# espn_board.net
KiCad netlist of a schematic drawn in EAGLE
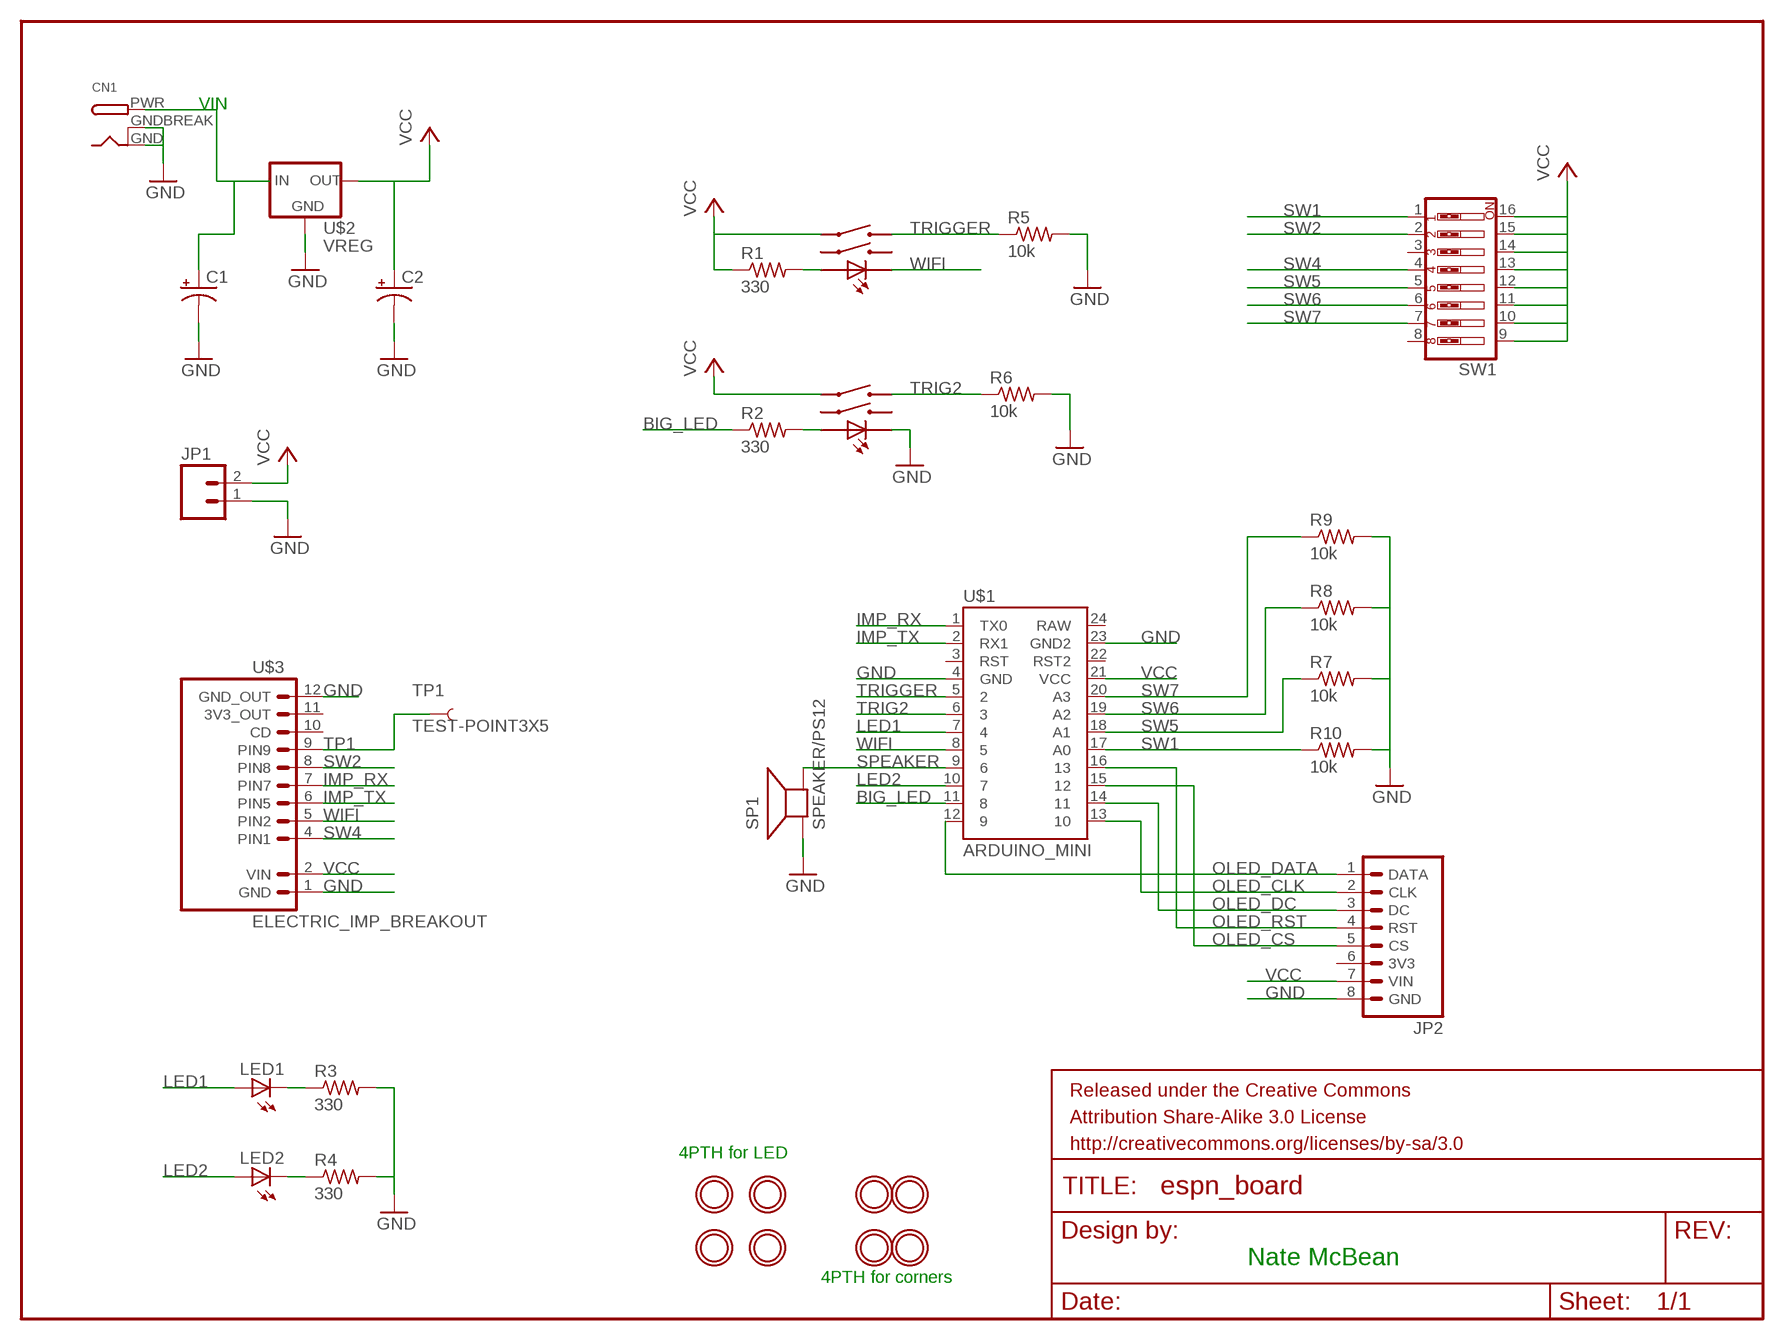
[diagram p0: schematic, sheet 1]

(export (version "E")
  (design (tool "Eeschema 10.0.6"))
  (components
    (comp (ref "ACK")
      (value "LED_TACTILE_BUTTON")
      (footprint "eagle-import:LED_TACTILE_BUTTON")
      (libsource (lib "eagle-import") (part "LED_TACTILE_BUTTON"))
    )
    (comp (ref "C1")
      (value "CAP_POLPTH2")
      (footprint "eagle-import:CPOL-RADIAL-10UF-25V")
      (libsource (lib "eagle-import") (part "CAP_POLPTH2"))
    )
    (comp (ref "C2")
      (value "CAP_POLPTH2")
      (footprint "eagle-import:CPOL-RADIAL-10UF-25V")
      (libsource (lib "eagle-import") (part "CAP_POLPTH2"))
    )
    (comp (ref "CN1")
      (value "DCBARRELPTH")
      (footprint "eagle-import:DCJACK_2MM_PTH")
      (libsource (lib "eagle-import") (part "DCBARRELPTH"))
    )
    (comp (ref "FRAME1")
      (value "FRAME-LETTER")
      (footprint "eagle-import:CREATIVE_COMMONS")
      (libsource (lib "eagle-import") (part "FRAME-LETTER"))
    )
    (comp (ref "JP1")
      (value "M02PTH")
      (footprint "eagle-import:1X02")
      (libsource (lib "eagle-import") (part "M02PTH"))
    )
    (comp (ref "JP2")
      (value "OLED128X641X08")
      (footprint "eagle-import:OLED_128X64")
      (libsource (lib "eagle-import") (part "OLED128X641X08"))
    )
    (comp (ref "LED1")
      (value "LED5MM")
      (footprint "eagle-import:LED5MM")
      (libsource (lib "eagle-import") (part "LED5MM"))
    )
    (comp (ref "LED2")
      (value "LED5MM")
      (footprint "eagle-import:LED5MM")
      (libsource (lib "eagle-import") (part "LED5MM"))
    )
    (comp (ref "R1")
      (value "330")
      (footprint "eagle-import:R0805")
      (libsource (lib "eagle-import") (part "R-US_R0805"))
    )
    (comp (ref "R2")
      (value "330")
      (footprint "eagle-import:R0805")
      (libsource (lib "eagle-import") (part "R-US_R0805"))
    )
    (comp (ref "R3")
      (value "330")
      (footprint "eagle-import:R0805")
      (libsource (lib "eagle-import") (part "R-US_R0805"))
    )
    (comp (ref "R4")
      (value "330")
      (footprint "eagle-import:R0805")
      (libsource (lib "eagle-import") (part "R-US_R0805"))
    )
    (comp (ref "R5")
      (value "10k")
      (footprint "eagle-import:R0805")
      (libsource (lib "eagle-import") (part "R-US_R0805"))
    )
    (comp (ref "R6")
      (value "10k")
      (footprint "eagle-import:R0805")
      (libsource (lib "eagle-import") (part "R-US_R0805"))
    )
    (comp (ref "R7")
      (value "10k")
      (footprint "eagle-import:R0805")
      (libsource (lib "eagle-import") (part "R-US_R0805"))
    )
    (comp (ref "R8")
      (value "10k")
      (footprint "eagle-import:R0805")
      (libsource (lib "eagle-import") (part "R-US_R0805"))
    )
    (comp (ref "R9")
      (value "10k")
      (footprint "eagle-import:R0805")
      (libsource (lib "eagle-import") (part "R-US_R0805"))
    )
    (comp (ref "R10")
      (value "10k")
      (footprint "eagle-import:R0805")
      (libsource (lib "eagle-import") (part "R-US_R0805"))
    )
    (comp (ref "SEND")
      (value "LED_TACTILE_BUTTON")
      (footprint "eagle-import:LED_TACTILE_BUTTON")
      (libsource (lib "eagle-import") (part "LED_TACTILE_BUTTON"))
    )
    (comp (ref "SP1")
      (value "SPEAKER/PS12")
      (footprint "eagle-import:PS12")
      (libsource (lib "eagle-import") (part "SPEAKER/PS12"))
    )
    (comp (ref "SW1")
      (value "SW_DIP-8")
      (footprint "eagle-import:DIPSWITCH-08")
      (libsource (lib "eagle-import") (part "SW_DIP-8"))
    )
    (comp (ref "TP1")
      (value "TEST-POINT3X5")
      (footprint "eagle-import:PAD.03X.05")
      (libsource (lib "eagle-import") (part "TEST-POINT3X5"))
    )
    (comp (ref "U$1")
      (value "ARDUINO_MINI")
      (footprint "eagle-import:ARDUINO_MINI")
      (libsource (lib "eagle-import") (part "ARDUINO_MINI"))
    )
    (comp (ref "U$2")
      (value "VREG")
      (footprint "eagle-import:78XXL")
      (libsource (lib "eagle-import") (part "V_REG_LD1117VXX"))
    )
    (comp (ref "U$3")
      (value "ELECTRIC_IMP_BREAKOUT")
      (footprint "eagle-import:ELECTRIC_IMP_BREAKOUT")
      (libsource (lib "eagle-import") (part "ELECTRIC_IMP_BREAKOUT"))
    )
    (comp (ref "U$5")
      (value "MOUNTINGHOLE2.5")
      (footprint "eagle-import:MOUNTINGHOLE_2.5_PLATED")
      (libsource (lib "eagle-import") (part "MOUNTINGHOLE2.5"))
    )
    (comp (ref "U$6")
      (value "MOUNTINGHOLE2.5")
      (footprint "eagle-import:MOUNTINGHOLE_2.5_PLATED")
      (libsource (lib "eagle-import") (part "MOUNTINGHOLE2.5"))
    )
    (comp (ref "U$7")
      (value "MOUNTINGHOLE2.5")
      (footprint "eagle-import:MOUNTINGHOLE_2.5_PLATED")
      (libsource (lib "eagle-import") (part "MOUNTINGHOLE2.5"))
    )
    (comp (ref "U$8")
      (value "MOUNTINGHOLE2.5")
      (footprint "eagle-import:MOUNTINGHOLE_2.5_PLATED")
      (libsource (lib "eagle-import") (part "MOUNTINGHOLE2.5"))
    )
    (comp (ref "U$9")
      (value "MOUNTINGHOLE2.5")
      (footprint "eagle-import:MOUNTINGHOLE_2.5_PLATED")
      (libsource (lib "eagle-import") (part "MOUNTINGHOLE2.5"))
    )
    (comp (ref "U$10")
      (value "MOUNTINGHOLE2.5")
      (footprint "eagle-import:MOUNTINGHOLE_2.5_PLATED")
      (libsource (lib "eagle-import") (part "MOUNTINGHOLE2.5"))
    )
    (comp (ref "U$11")
      (value "MOUNTINGHOLE2.5")
      (footprint "eagle-import:MOUNTINGHOLE_2.5_PLATED")
      (libsource (lib "eagle-import") (part "MOUNTINGHOLE2.5"))
    )
    (comp (ref "U$12")
      (value "MOUNTINGHOLE2.5")
      (footprint "eagle-import:MOUNTINGHOLE_2.5_PLATED")
      (libsource (lib "eagle-import") (part "MOUNTINGHOLE2.5"))
    )
  )
  (nets
    (net (code "1") (name "/BIG_LED") (class "Default")
      (node (ref "R2") (pin "1") (pinfunction "1_1") (pintype "passive"))
      (node (ref "U$1") (pin "11") (pinfunction "8_11") (pintype "bidirectional"))
    )
    (net (code "2") (name "/IMP_RX") (class "Default")
      (node (ref "U$1") (pin "1") (pinfunction "TX0_1") (pintype "bidirectional"))
      (node (ref "U$3") (pin "7") (pinfunction "PIN7_7") (pintype "passive"))
    )
    (net (code "3") (name "/IMP_TX") (class "Default")
      (node (ref "U$1") (pin "2") (pinfunction "RX1_2") (pintype "bidirectional"))
      (node (ref "U$3") (pin "6") (pinfunction "PIN5_6") (pintype "passive"))
    )
    (net (code "4") (name "/LED1") (class "Default")
      (node (ref "LED1") (pin "A") (pinfunction "A_A") (pintype "passive"))
      (node (ref "U$1") (pin "7") (pinfunction "4_7") (pintype "bidirectional"))
    )
    (net (code "5") (name "/LED2") (class "Default")
      (node (ref "LED2") (pin "A") (pinfunction "A_A") (pintype "passive"))
      (node (ref "U$1") (pin "10") (pinfunction "7_10") (pintype "bidirectional"))
    )
    (net (code "6") (name "/OLED_CLK") (class "Default")
      (node (ref "JP2") (pin "2") (pinfunction "CLK_2") (pintype "passive"))
      (node (ref "U$1") (pin "13") (pinfunction "10_13") (pintype "bidirectional"))
    )
    (net (code "7") (name "/OLED_CS") (class "Default")
      (node (ref "JP2") (pin "5") (pinfunction "CS_5") (pintype "passive"))
      (node (ref "U$1") (pin "15") (pinfunction "12_15") (pintype "bidirectional"))
    )
    (net (code "8") (name "/OLED_DATA") (class "Default")
      (node (ref "JP2") (pin "1") (pinfunction "DATA_1") (pintype "passive"))
      (node (ref "U$1") (pin "12") (pinfunction "9_12") (pintype "bidirectional"))
    )
    (net (code "9") (name "/OLED_DC") (class "Default")
      (node (ref "JP2") (pin "3") (pinfunction "DC_3") (pintype "passive"))
      (node (ref "U$1") (pin "14") (pinfunction "11_14") (pintype "bidirectional"))
    )
    (net (code "10") (name "/OLED_RST") (class "Default")
      (node (ref "JP2") (pin "4") (pinfunction "RST_4") (pintype "passive"))
      (node (ref "U$1") (pin "16") (pinfunction "13_16") (pintype "bidirectional"))
    )
    (net (code "11") (name "/SPEAKER") (class "Default")
      (node (ref "SP1") (pin "P$2") (pinfunction "-_P$2") (pintype "passive"))
      (node (ref "U$1") (pin "9") (pinfunction "6_9") (pintype "bidirectional"))
    )
    (net (code "12") (name "/SW1") (class "Default")
      (node (ref "R10") (pin "1") (pinfunction "1_1") (pintype "passive"))
      (node (ref "SW1") (pin "1") (pinfunction "1_1") (pintype "passive"))
      (node (ref "U$1") (pin "17") (pinfunction "A0_17") (pintype "bidirectional"))
    )
    (net (code "13") (name "/SW2") (class "Default")
      (node (ref "SW1") (pin "2") (pinfunction "2_2") (pintype "passive"))
      (node (ref "U$3") (pin "8") (pinfunction "PIN8_8") (pintype "passive"))
    )
    (net (code "14") (name "/SW4") (class "Default")
      (node (ref "SW1") (pin "4") (pinfunction "4_4") (pintype "passive"))
      (node (ref "U$3") (pin "4") (pinfunction "PIN1_4") (pintype "passive"))
    )
    (net (code "15") (name "/SW5") (class "Default")
      (node (ref "R7") (pin "1") (pinfunction "1_1") (pintype "passive"))
      (node (ref "SW1") (pin "5") (pinfunction "5_5") (pintype "passive"))
      (node (ref "U$1") (pin "18") (pinfunction "A1_18") (pintype "bidirectional"))
    )
    (net (code "16") (name "/SW6") (class "Default")
      (node (ref "R8") (pin "1") (pinfunction "1_1") (pintype "passive"))
      (node (ref "SW1") (pin "6") (pinfunction "6_6") (pintype "passive"))
      (node (ref "U$1") (pin "19") (pinfunction "A2_19") (pintype "bidirectional"))
    )
    (net (code "17") (name "/SW7") (class "Default")
      (node (ref "R9") (pin "1") (pinfunction "1_1") (pintype "passive"))
      (node (ref "SW1") (pin "7") (pinfunction "7_7") (pintype "passive"))
      (node (ref "U$1") (pin "20") (pinfunction "A3_20") (pintype "bidirectional"))
    )
    (net (code "18") (name "/TP1") (class "Default")
      (node (ref "TP1") (pin "P$1") (pinfunction "1_P$1") (pintype "bidirectional"))
      (node (ref "U$3") (pin "9") (pinfunction "PIN9_9") (pintype "passive"))
    )
    (net (code "19") (name "/TRIG2") (class "Default")
      (node (ref "ACK") (pin "SWA2") (pinfunction "SWA2_SWA2") (pintype "passive"))
      (node (ref "R6") (pin "1") (pinfunction "1_1") (pintype "passive"))
      (node (ref "U$1") (pin "6") (pinfunction "3_6") (pintype "bidirectional"))
    )
    (net (code "20") (name "/TRIGGER") (class "Default")
      (node (ref "R5") (pin "1") (pinfunction "1_1") (pintype "passive"))
      (node (ref "SEND") (pin "SWA2") (pinfunction "SWA2_SWA2") (pintype "passive"))
      (node (ref "U$1") (pin "5") (pinfunction "2_5") (pintype "bidirectional"))
    )
    (net (code "21") (name "/VIN") (class "Default")
      (node (ref "C1") (pin "1") (pinfunction "+_1") (pintype "passive"))
      (node (ref "CN1") (pin "PWR") (pinfunction "PWR_PWR") (pintype "power_in"))
      (node (ref "U$2") (pin "OUT") (pinfunction "IN_OUT") (pintype "input"))
    )
    (net (code "22") (name "/WIFI") (class "Default")
      (node (ref "SEND") (pin "LEDC") (pinfunction "LEDC_LEDC") (pintype "passive"))
      (node (ref "U$1") (pin "8") (pinfunction "5_8") (pintype "bidirectional"))
      (node (ref "U$3") (pin "5") (pinfunction "PIN2_5") (pintype "passive"))
    )
    (net (code "23") (name "GND") (class "Default")
      (node (ref "ACK") (pin "LEDC") (pinfunction "LEDC_LEDC") (pintype "passive"))
      (node (ref "C1") (pin "2") (pinfunction "-_2") (pintype "passive"))
      (node (ref "C2") (pin "2") (pinfunction "-_2") (pintype "passive"))
      (node (ref "CN1") (pin "GND") (pinfunction "GND_GND") (pintype "power_in"))
      (node (ref "CN1") (pin "GNDBREAK") (pinfunction "GNDBREAK_GNDBREAK") (pintype "power_in"))
      (node (ref "JP1") (pin "1") (pinfunction "1_1") (pintype "passive"))
      (node (ref "JP2") (pin "8") (pinfunction "GND_8") (pintype "passive"))
      (node (ref "R10") (pin "2") (pinfunction "2_2") (pintype "passive"))
      (node (ref "R3") (pin "2") (pinfunction "2_2") (pintype "passive"))
      (node (ref "R4") (pin "2") (pinfunction "2_2") (pintype "passive"))
      (node (ref "R5") (pin "2") (pinfunction "2_2") (pintype "passive"))
      (node (ref "R6") (pin "2") (pinfunction "2_2") (pintype "passive"))
      (node (ref "R7") (pin "2") (pinfunction "2_2") (pintype "passive"))
      (node (ref "R8") (pin "2") (pinfunction "2_2") (pintype "passive"))
      (node (ref "R9") (pin "2") (pinfunction "2_2") (pintype "passive"))
      (node (ref "SP1") (pin "P$1") (pinfunction "+_P$1") (pintype "passive"))
      (node (ref "U$1") (pin "23") (pinfunction "GND2_23") (pintype "bidirectional"))
      (node (ref "U$1") (pin "4") (pinfunction "GND_4") (pintype "bidirectional"))
      (node (ref "U$2") (pin "IN") (pinfunction "GND_IN") (pintype "input"))
      (node (ref "U$3") (pin "1") (pinfunction "GND_1") (pintype "passive"))
      (node (ref "U$3") (pin "12") (pinfunction "GND_OUT_12") (pintype "passive"))
    )
    (net (code "24") (name "Net-(ACK-PadLEDA)") (class "Default")
      (node (ref "ACK") (pin "LEDA") (pinfunction "LEDA_LEDA") (pintype "passive"))
      (node (ref "R2") (pin "2") (pinfunction "2_2") (pintype "passive"))
    )
    (net (code "25") (name "Net-(LED1-C)") (class "Default")
      (node (ref "LED1") (pin "K") (pinfunction "C_K") (pintype "passive"))
      (node (ref "R3") (pin "1") (pinfunction "1_1") (pintype "passive"))
    )
    (net (code "26") (name "Net-(LED2-C)") (class "Default")
      (node (ref "LED2") (pin "K") (pinfunction "C_K") (pintype "passive"))
      (node (ref "R4") (pin "1") (pinfunction "1_1") (pintype "passive"))
    )
    (net (code "27") (name "Net-(R1-Pad2)") (class "Default")
      (node (ref "R1") (pin "2") (pinfunction "2_2") (pintype "passive"))
      (node (ref "SEND") (pin "LEDA") (pinfunction "LEDA_LEDA") (pintype "passive"))
    )
    (net (code "28") (name "VCC") (class "Default")
      (node (ref "ACK") (pin "SWA1") (pinfunction "SWA1_SWA1") (pintype "passive"))
      (node (ref "C2") (pin "1") (pinfunction "+_1") (pintype "passive"))
      (node (ref "JP1") (pin "2") (pinfunction "2_2") (pintype "passive"))
      (node (ref "JP2") (pin "7") (pinfunction "VIN_7") (pintype "passive"))
      (node (ref "R1") (pin "1") (pinfunction "1_1") (pintype "passive"))
      (node (ref "SEND") (pin "SWA1") (pinfunction "SWA1_SWA1") (pintype "passive"))
      (node (ref "SW1") (pin "10") (pinfunction "10_10") (pintype "passive"))
      (node (ref "SW1") (pin "11") (pinfunction "11_11") (pintype "passive"))
      (node (ref "SW1") (pin "12") (pinfunction "12_12") (pintype "passive"))
      (node (ref "SW1") (pin "13") (pinfunction "13_13") (pintype "passive"))
      (node (ref "SW1") (pin "14") (pinfunction "14_14") (pintype "passive"))
      (node (ref "SW1") (pin "15") (pinfunction "15_15") (pintype "passive"))
      (node (ref "SW1") (pin "16") (pinfunction "16_16") (pintype "passive"))
      (node (ref "SW1") (pin "9") (pinfunction "9_9") (pintype "passive"))
      (node (ref "U$1") (pin "21") (pinfunction "VCC_21") (pintype "bidirectional"))
      (node (ref "U$2") (pin "GND") (pinfunction "OUT_GND") (pintype "output"))
      (node (ref "U$3") (pin "2") (pinfunction "VIN_2") (pintype "passive"))
    )
    (net (code "29") (name "unconnected-(ACK-PadSWB1)") (class "Default")
      (node (ref "ACK") (pin "SWB1") (pinfunction "SWB1_SWB1") (pintype "passive"))
    )
    (net (code "30") (name "unconnected-(ACK-PadSWB2)") (class "Default")
      (node (ref "ACK") (pin "SWB2") (pinfunction "SWB2_SWB2") (pintype "passive"))
    )
    (net (code "31") (name "unconnected-(JP2-3V3-Pad6)") (class "Default")
      (node (ref "JP2") (pin "6") (pinfunction "3V3_6") (pintype "passive"))
    )
    (net (code "32") (name "unconnected-(SEND-PadSWB1)") (class "Default")
      (node (ref "SEND") (pin "SWB1") (pinfunction "SWB1_SWB1") (pintype "passive"))
    )
    (net (code "33") (name "unconnected-(SEND-PadSWB2)") (class "Default")
      (node (ref "SEND") (pin "SWB2") (pinfunction "SWB2_SWB2") (pintype "passive"))
    )
    (net (code "34") (name "unconnected-(SW1-Pad3)") (class "Default")
      (node (ref "SW1") (pin "3") (pinfunction "3_3") (pintype "passive"))
    )
    (net (code "35") (name "unconnected-(SW1-Pad8)") (class "Default")
      (node (ref "SW1") (pin "8") (pinfunction "8_8") (pintype "passive"))
    )
    (net (code "36") (name "unconnected-(U$1-RAW-Pad24)") (class "Default")
      (node (ref "U$1") (pin "24") (pinfunction "RAW_24") (pintype "bidirectional"))
    )
    (net (code "37") (name "unconnected-(U$1-RST-Pad3)") (class "Default")
      (node (ref "U$1") (pin "3") (pinfunction "RST_3") (pintype "bidirectional"))
    )
    (net (code "38") (name "unconnected-(U$1-RST2-Pad22)") (class "Default")
      (node (ref "U$1") (pin "22") (pinfunction "RST2_22") (pintype "bidirectional"))
    )
    (net (code "39") (name "unconnected-(U$3-3V3_OUT-Pad11)") (class "Default")
      (node (ref "U$3") (pin "11") (pinfunction "3V3_OUT_11") (pintype "passive"))
    )
    (net (code "40") (name "unconnected-(U$3-CD-Pad10)") (class "Default")
      (node (ref "U$3") (pin "10") (pinfunction "CD_10") (pintype "passive"))
    )
  )
)
